# Amiga_Parallel_SD_Rev_3.net
KiCad netlist of a schematic drawn in EAGLE
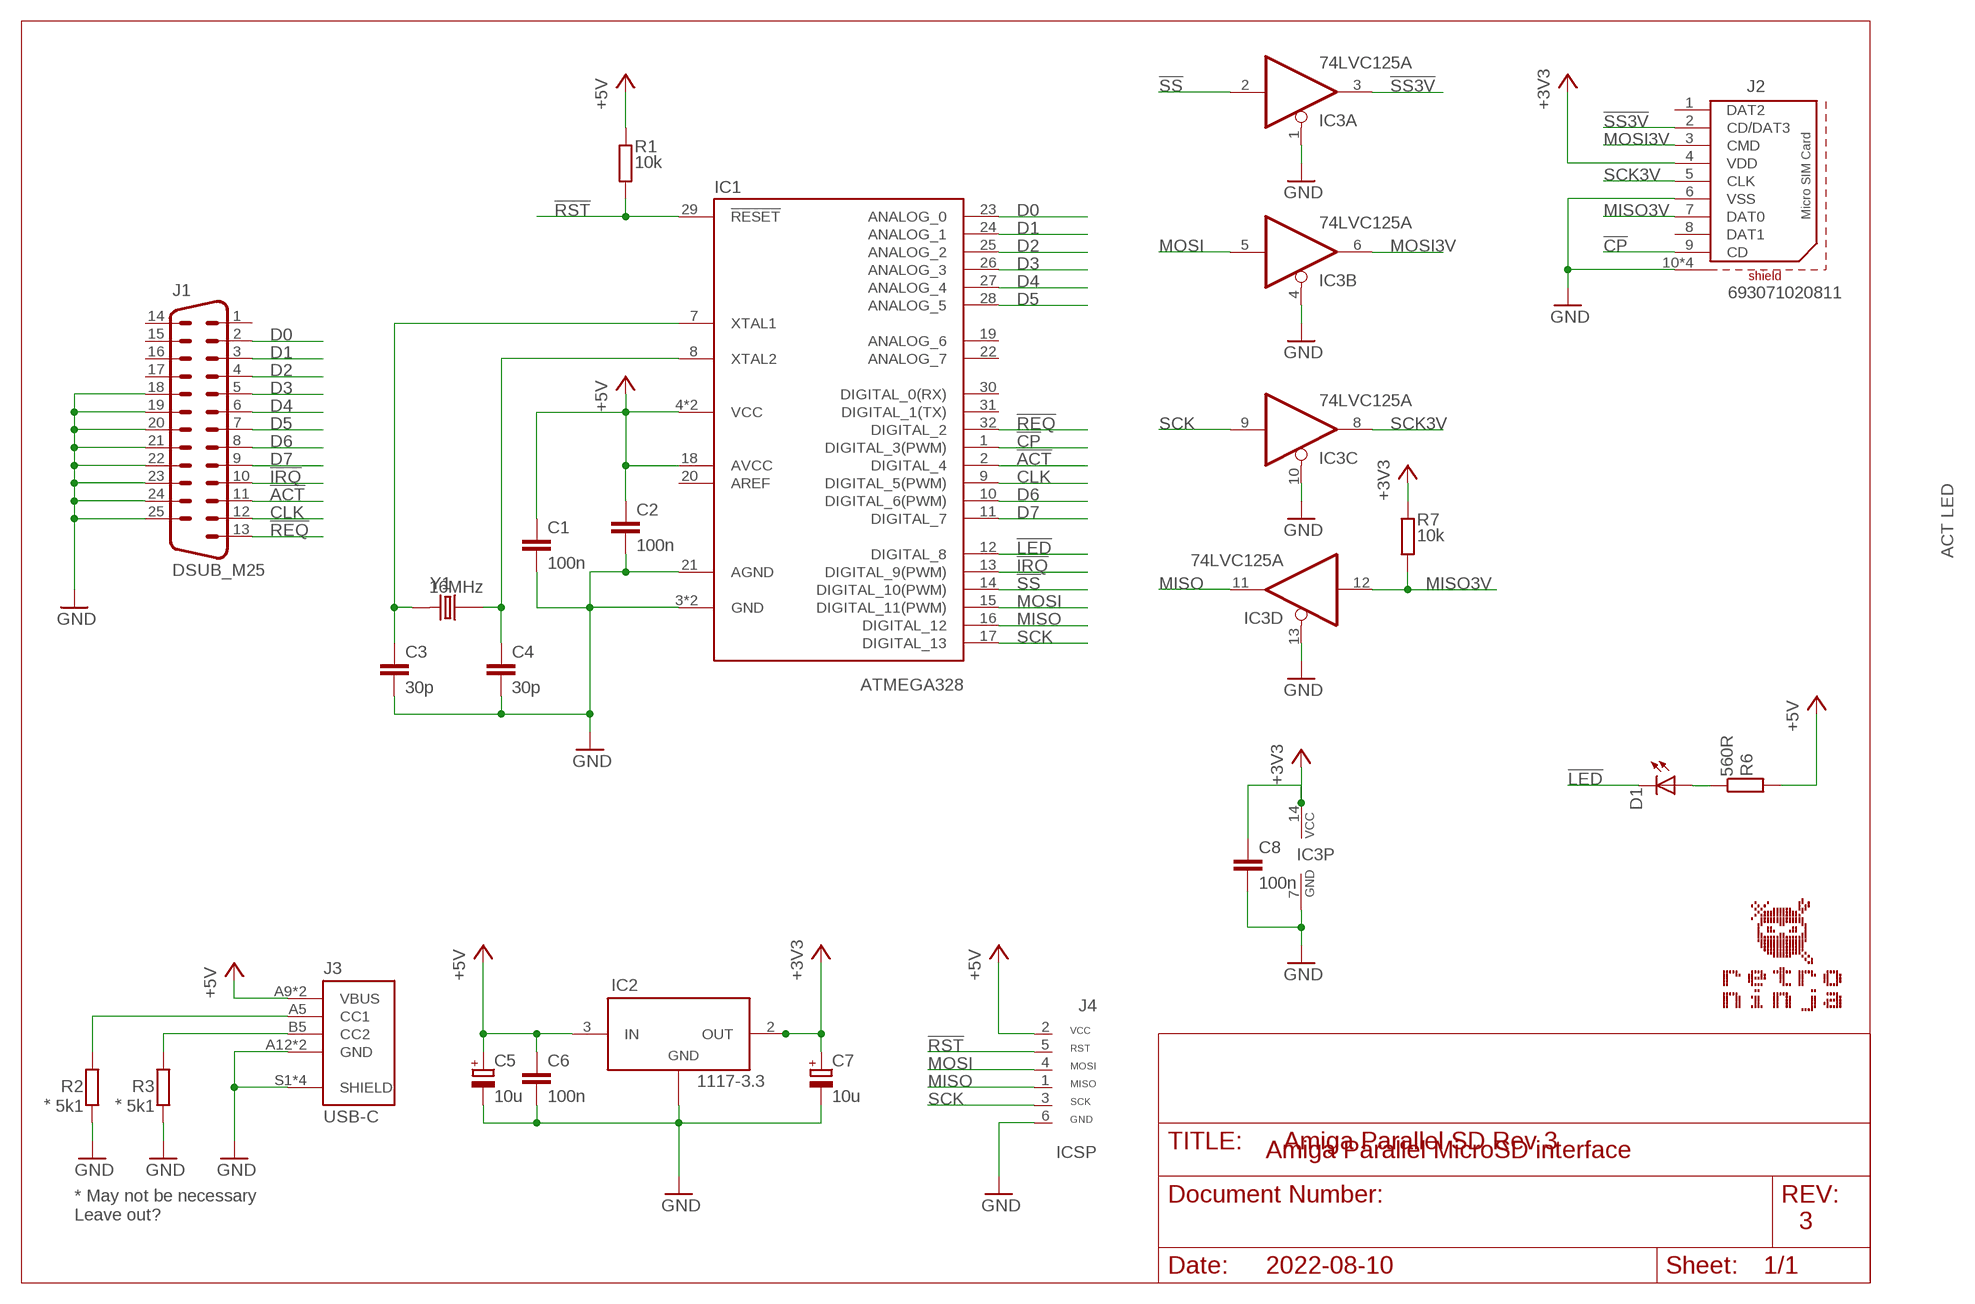
[diagram p0: schematic, sheet 1]

(export (version "E")
  (design (tool "Eeschema 10.0.6"))
  (components
    (comp (ref "C1")
      (value "100n")
      (footprint "eagle-import:C0805")
      (libsource (lib "eagle-import") (part "C-EUC0805"))
    )
    (comp (ref "C2")
      (value "100n")
      (footprint "eagle-import:C0805")
      (libsource (lib "eagle-import") (part "C-EUC0805"))
    )
    (comp (ref "C3")
      (value "30p")
      (footprint "eagle-import:C0805")
      (libsource (lib "eagle-import") (part "C-EUC0805"))
    )
    (comp (ref "C4")
      (value "30p")
      (footprint "eagle-import:C0805")
      (libsource (lib "eagle-import") (part "C-EUC0805"))
    )
    (comp (ref "C5")
      (value "10u")
      (footprint "eagle-import:TANTALUM_0805")
      (libsource (lib "eagle-import") (part "CAPACITOR_POL_TANT_0805"))
    )
    (comp (ref "C6")
      (value "100n")
      (footprint "eagle-import:C0805")
      (libsource (lib "eagle-import") (part "C-EUC0805"))
    )
    (comp (ref "C7")
      (value "10u")
      (footprint "eagle-import:TANTALUM_0805")
      (libsource (lib "eagle-import") (part "CAPACITOR_POL_TANT_0805"))
    )
    (comp (ref "C8")
      (value "100n")
      (footprint "eagle-import:C0805")
      (libsource (lib "eagle-import") (part "C-EUC0805"))
    )
    (comp (ref "D1")
      (value "LED_3MM_GREEN")
      (footprint "eagle-import:LED3MM_GREEN")
      (libsource (lib "eagle-import") (part "LED_3MM_GREEN"))
    )
    (comp (ref "IC1")
      (value "ATMEGA328")
      (footprint "eagle-import:TQFP-32")
      (libsource (lib "eagle-import") (part "ARDUINO_168_328_TQFP"))
    )
    (comp (ref "IC2")
      (value "1117-3.3")
      (footprint "eagle-import:SOT-223")
      (fields
        (field (name "DIGIKEY_PART_NUMBER") "NCP1117ST33T3GOSTR-ND")
        (field (name "MANUFACTURER") "ON Semiconductor")
        (field (name "MPN") "NCP1117ST33T3G")
        (field (name "CREATED_BY") "PCBLayout.com")
      )
      (libsource (lib "eagle-import") (part "NCP1117ST33T3G"))
    )
    (comp (ref "IC3")
      (value "74LVC125A")
      (footprint "eagle-import:SO14")
      (libsource (lib "eagle-import") (part "74125DHC"))
    )
    (comp (ref "J1")
      (value "DSUB_M25")
      (footprint "eagle-import:DSUB_M25D")
      (libsource (lib "eagle-import") (part "DSUB_M25"))
    )
    (comp (ref "J2")
      (value "693071020811")
      (footprint "eagle-import:693071020811")
      (libsource (lib "eagle-import") (part "693071020811"))
    )
    (comp (ref "J3")
      (value "USB-C")
      (footprint "eagle-import:MOLEX_2171750001")
      (fields (field (name "MANUFACTURER") "Molex"))
      (libsource (lib "eagle-import") (part "USB-C"))
    )
    (comp (ref "J4")
      (value "ICSP")
      (footprint "eagle-import:HEADER_2X3_ALT")
      (libsource (lib "eagle-import") (part "ICSP_CONNECTOR_6_ALT"))
    )
    (comp (ref "R1")
      (value "10k")
      (footprint "eagle-import:R0805")
      (libsource (lib "eagle-import") (part "R-EU_R0805"))
    )
    (comp (ref "R2")
      (value "5k1")
      (footprint "eagle-import:R0805")
      (libsource (lib "eagle-import") (part "R-EU_R0805"))
    )
    (comp (ref "R3")
      (value "5k1")
      (footprint "eagle-import:R0805")
      (libsource (lib "eagle-import") (part "R-EU_R0805"))
    )
    (comp (ref "R6")
      (value "560R")
      (footprint "eagle-import:R0805")
      (libsource (lib "eagle-import") (part "R-EU_R0805"))
    )
    (comp (ref "R7")
      (value "10k")
      (footprint "eagle-import:R0805")
      (libsource (lib "eagle-import") (part "R-EU_R0805"))
    )
    (comp (ref "Y1")
      (value "16MHz")
      (footprint "eagle-import:CRYSTAL_SMD-2_7X4X2.3")
      (libsource (lib "eagle-import") (part "CRYSTAL"))
    )
  )
  (nets
    (net (code "1") (name "+3V3") (class "Default")
      (node (ref "C7") (pin "+") (pinfunction "+_+") (pintype "passive"))
      (node (ref "C8") (pin "1") (pinfunction "1_1") (pintype "passive"))
      (node (ref "IC2") (pin "2") (pinfunction "OUT_2") (pintype "output"))
      (node (ref "IC2") (pin "4") (pinfunction "4_4") (pintype "passive"))
      (node (ref "IC3") (pin "14") (pinfunction "VCC_14") (pintype "power_in"))
      (node (ref "J2") (pin "4") (pinfunction "VDD_4") (pintype "bidirectional"))
      (node (ref "R7") (pin "1") (pinfunction "1_1") (pintype "passive"))
    )
    (net (code "2") (name "+5V") (class "Default")
      (node (ref "C1") (pin "1") (pinfunction "1_1") (pintype "passive"))
      (node (ref "C2") (pin "1") (pinfunction "1_1") (pintype "passive"))
      (node (ref "C5") (pin "+") (pinfunction "+_+") (pintype "passive"))
      (node (ref "C6") (pin "1") (pinfunction "1_1") (pintype "passive"))
      (node (ref "IC1") (pin "18") (pinfunction "AVCC_18") (pintype "passive"))
      (node (ref "IC1") (pin "4") (pinfunction "VCC_4") (pintype "passive"))
      (node (ref "IC1") (pin "6") (pinfunction "VCC_6") (pintype "passive"))
      (node (ref "IC2") (pin "3") (pinfunction "IN_3") (pintype "input"))
      (node (ref "J3") (pin "A9") (pinfunction "VBUS_A9") (pintype "power_in"))
      (node (ref "J3") (pin "B9") (pinfunction "VBUS_B9") (pintype "power_in"))
      (node (ref "J4") (pin "2") (pinfunction "VCC_2") (pintype "power_in"))
      (node (ref "R1") (pin "1") (pinfunction "1_1") (pintype "passive"))
      (node (ref "R6") (pin "2") (pinfunction "2_2") (pintype "passive"))
    )
    (net (code "3") (name "/CLK") (class "Default")
      (node (ref "IC1") (pin "9") (pinfunction "DIGITAL_5(PWM)_9") (pintype "bidirectional"))
      (node (ref "J1") (pin "12") (pinfunction "12_12") (pintype "passive"))
    )
    (net (code "4") (name "/D0") (class "Default")
      (node (ref "IC1") (pin "23") (pinfunction "ANALOG_0_23") (pintype "bidirectional"))
      (node (ref "J1") (pin "2") (pinfunction "2_2") (pintype "passive"))
    )
    (net (code "5") (name "/D1") (class "Default")
      (node (ref "IC1") (pin "24") (pinfunction "ANALOG_1_24") (pintype "bidirectional"))
      (node (ref "J1") (pin "3") (pinfunction "3_3") (pintype "passive"))
    )
    (net (code "6") (name "/D2") (class "Default")
      (node (ref "IC1") (pin "25") (pinfunction "ANALOG_2_25") (pintype "bidirectional"))
      (node (ref "J1") (pin "4") (pinfunction "4_4") (pintype "passive"))
    )
    (net (code "7") (name "/D3") (class "Default")
      (node (ref "IC1") (pin "26") (pinfunction "ANALOG_3_26") (pintype "bidirectional"))
      (node (ref "J1") (pin "5") (pinfunction "5_5") (pintype "passive"))
    )
    (net (code "8") (name "/D4") (class "Default")
      (node (ref "IC1") (pin "27") (pinfunction "ANALOG_4_27") (pintype "bidirectional"))
      (node (ref "J1") (pin "6") (pinfunction "6_6") (pintype "passive"))
    )
    (net (code "9") (name "/D5") (class "Default")
      (node (ref "IC1") (pin "28") (pinfunction "ANALOG_5_28") (pintype "bidirectional"))
      (node (ref "J1") (pin "7") (pinfunction "7_7") (pintype "passive"))
    )
    (net (code "10") (name "/D6") (class "Default")
      (node (ref "IC1") (pin "10") (pinfunction "DIGITAL_6(PWM)_10") (pintype "bidirectional"))
      (node (ref "J1") (pin "8") (pinfunction "8_8") (pintype "passive"))
    )
    (net (code "11") (name "/D7") (class "Default")
      (node (ref "IC1") (pin "11") (pinfunction "DIGITAL_7_11") (pintype "bidirectional"))
      (node (ref "J1") (pin "9") (pinfunction "9_9") (pintype "passive"))
    )
    (net (code "12") (name "/MISO") (class "Default")
      (node (ref "IC1") (pin "16") (pinfunction "DIGITAL_12_16") (pintype "bidirectional"))
      (node (ref "IC3") (pin "11") (pinfunction "O_11") (pintype "tri_state"))
      (node (ref "J4") (pin "1") (pinfunction "MISO_1") (pintype "output"))
    )
    (net (code "13") (name "/MISO3V") (class "Default")
      (node (ref "IC3") (pin "12") (pinfunction "I_12") (pintype "input"))
      (node (ref "J2") (pin "7") (pinfunction "DAT0_7") (pintype "bidirectional"))
      (node (ref "R7") (pin "2") (pinfunction "2_2") (pintype "passive"))
    )
    (net (code "14") (name "/MOSI") (class "Default")
      (node (ref "IC1") (pin "15") (pinfunction "DIGITAL_11(PWM)_15") (pintype "bidirectional"))
      (node (ref "IC3") (pin "5") (pinfunction "I_5") (pintype "input"))
      (node (ref "J4") (pin "4") (pinfunction "MOSI_4") (pintype "input"))
    )
    (net (code "15") (name "/MOSI3V") (class "Default")
      (node (ref "IC3") (pin "6") (pinfunction "O_6") (pintype "tri_state"))
      (node (ref "J2") (pin "3") (pinfunction "CMD_3") (pintype "bidirectional"))
    )
    (net (code "16") (name "/SCK") (class "Default")
      (node (ref "IC1") (pin "17") (pinfunction "DIGITAL_13_17") (pintype "bidirectional"))
      (node (ref "IC3") (pin "9") (pinfunction "I_9") (pintype "input"))
      (node (ref "J4") (pin "3") (pinfunction "SCK_3") (pintype "input"))
    )
    (net (code "17") (name "/SCK3V") (class "Default")
      (node (ref "IC3") (pin "8") (pinfunction "O_8") (pintype "tri_state"))
      (node (ref "J2") (pin "5") (pinfunction "CLK_5") (pintype "bidirectional"))
    )
    (net (code "18") (name "/~{ACT}") (class "Default")
      (node (ref "IC1") (pin "2") (pinfunction "DIGITAL_4_2") (pintype "bidirectional"))
      (node (ref "J1") (pin "11") (pinfunction "11_11") (pintype "passive"))
    )
    (net (code "19") (name "/~{CP}") (class "Default")
      (node (ref "IC1") (pin "1") (pinfunction "DIGITAL_3(PWM)_1") (pintype "bidirectional"))
      (node (ref "J2") (pin "9") (pinfunction "CD_9") (pintype "bidirectional"))
    )
    (net (code "20") (name "/~{IRQ}") (class "Default")
      (node (ref "IC1") (pin "13") (pinfunction "DIGITAL_9(PWM)_13") (pintype "bidirectional"))
      (node (ref "J1") (pin "10") (pinfunction "10_10") (pintype "passive"))
    )
    (net (code "21") (name "/~{LED}") (class "Default")
      (node (ref "D1") (pin "K") (pinfunction "C_K") (pintype "passive"))
      (node (ref "IC1") (pin "12") (pinfunction "DIGITAL_8_12") (pintype "bidirectional"))
    )
    (net (code "22") (name "/~{REQ}") (class "Default")
      (node (ref "IC1") (pin "32") (pinfunction "DIGITAL_2_32") (pintype "bidirectional"))
      (node (ref "J1") (pin "13") (pinfunction "13_13") (pintype "passive"))
    )
    (net (code "23") (name "/~{RST}") (class "Default")
      (node (ref "IC1") (pin "29") (pinfunction "~{RESET}_29") (pintype "bidirectional"))
      (node (ref "J4") (pin "5") (pinfunction "RST_5") (pintype "input"))
      (node (ref "R1") (pin "2") (pinfunction "2_2") (pintype "passive"))
    )
    (net (code "24") (name "/~{SS3V}") (class "Default")
      (node (ref "IC3") (pin "3") (pinfunction "O_3") (pintype "tri_state"))
      (node (ref "J2") (pin "2") (pinfunction "CD/DAT3_2") (pintype "bidirectional"))
    )
    (net (code "25") (name "/~{SS}") (class "Default")
      (node (ref "IC1") (pin "14") (pinfunction "DIGITAL_10(PWM)_14") (pintype "bidirectional"))
      (node (ref "IC3") (pin "2") (pinfunction "I_2") (pintype "input"))
    )
    (net (code "26") (name "GND") (class "Default")
      (node (ref "C1") (pin "2") (pinfunction "2_2") (pintype "passive"))
      (node (ref "C2") (pin "2") (pinfunction "2_2") (pintype "passive"))
      (node (ref "C3") (pin "2") (pinfunction "2_2") (pintype "passive"))
      (node (ref "C4") (pin "2") (pinfunction "2_2") (pintype "passive"))
      (node (ref "C5") (pin "-") (pinfunction "-_-") (pintype "passive"))
      (node (ref "C6") (pin "2") (pinfunction "2_2") (pintype "passive"))
      (node (ref "C7") (pin "-") (pinfunction "-_-") (pintype "passive"))
      (node (ref "C8") (pin "2") (pinfunction "2_2") (pintype "passive"))
      (node (ref "IC1") (pin "21") (pinfunction "AGND_21") (pintype "passive"))
      (node (ref "IC1") (pin "3") (pinfunction "GND_3") (pintype "passive"))
      (node (ref "IC1") (pin "5") (pinfunction "GND_5") (pintype "passive"))
      (node (ref "IC2") (pin "1") (pinfunction "ADJ/GND_1") (pintype "power_in"))
      (node (ref "IC3") (pin "1") (pinfunction "OE_1") (pintype "input"))
      (node (ref "IC3") (pin "10") (pinfunction "OE_10") (pintype "input"))
      (node (ref "IC3") (pin "13") (pinfunction "OE_13") (pintype "input"))
      (node (ref "IC3") (pin "4") (pinfunction "OE_4") (pintype "input"))
      (node (ref "IC3") (pin "7") (pinfunction "GND_7") (pintype "power_in"))
      (node (ref "J1") (pin "18") (pinfunction "18_18") (pintype "passive"))
      (node (ref "J1") (pin "19") (pinfunction "19_19") (pintype "passive"))
      (node (ref "J1") (pin "20") (pinfunction "20_20") (pintype "passive"))
      (node (ref "J1") (pin "21") (pinfunction "21_21") (pintype "passive"))
      (node (ref "J1") (pin "22") (pinfunction "22_22") (pintype "passive"))
      (node (ref "J1") (pin "23") (pinfunction "23_23") (pintype "passive"))
      (node (ref "J1") (pin "24") (pinfunction "24_24") (pintype "passive"))
      (node (ref "J1") (pin "25") (pinfunction "25_25") (pintype "passive"))
      (node (ref "J2") (pin "10") (pinfunction "SHIELD_10") (pintype "bidirectional"))
      (node (ref "J2") (pin "11") (pinfunction "SHIELD_11") (pintype "bidirectional"))
      (node (ref "J2") (pin "12") (pinfunction "SHIELD_12") (pintype "bidirectional"))
      (node (ref "J2") (pin "13") (pinfunction "SHIELD_13") (pintype "bidirectional"))
      (node (ref "J2") (pin "6") (pinfunction "VSS_6") (pintype "bidirectional"))
      (node (ref "J3") (pin "A12") (pinfunction "GND_A12") (pintype "power_in"))
      (node (ref "J3") (pin "B12") (pinfunction "GND_B12") (pintype "power_in"))
      (node (ref "J3") (pin "S1") (pinfunction "SHIELD_S1") (pintype "passive"))
      (node (ref "J3") (pin "S2") (pinfunction "SHIELD_S2") (pintype "passive"))
      (node (ref "J3") (pin "S3") (pinfunction "SHIELD_S3") (pintype "passive"))
      (node (ref "J3") (pin "S4") (pinfunction "SHIELD_S4") (pintype "passive"))
      (node (ref "J4") (pin "6") (pinfunction "GND_6") (pintype "power_in"))
      (node (ref "R2") (pin "1") (pinfunction "1_1") (pintype "passive"))
      (node (ref "R3") (pin "1") (pinfunction "1_1") (pintype "passive"))
    )
    (net (code "27") (name "Net-(D1-PadA)") (class "Default")
      (node (ref "D1") (pin "A") (pinfunction "A_A") (pintype "passive"))
      (node (ref "R6") (pin "1") (pinfunction "1_1") (pintype "passive"))
    )
    (net (code "28") (name "Net-(IC1-XTAL1)") (class "Default")
      (node (ref "C3") (pin "1") (pinfunction "1_1") (pintype "passive"))
      (node (ref "IC1") (pin "7") (pinfunction "XTAL1_7") (pintype "bidirectional"))
      (node (ref "Y1") (pin "2") (pinfunction "2_2") (pintype "passive"))
    )
    (net (code "29") (name "Net-(IC1-XTAL2)") (class "Default")
      (node (ref "C4") (pin "1") (pinfunction "1_1") (pintype "passive"))
      (node (ref "IC1") (pin "8") (pinfunction "XTAL2_8") (pintype "bidirectional"))
      (node (ref "Y1") (pin "1") (pinfunction "1_1") (pintype "passive"))
    )
    (net (code "30") (name "Net-(J3-CC1)") (class "Default")
      (node (ref "J3") (pin "A5") (pinfunction "CC1_A5") (pintype "bidirectional"))
      (node (ref "R2") (pin "2") (pinfunction "2_2") (pintype "passive"))
    )
    (net (code "31") (name "Net-(J3-CC2)") (class "Default")
      (node (ref "J3") (pin "B5") (pinfunction "CC2_B5") (pintype "bidirectional"))
      (node (ref "R3") (pin "2") (pinfunction "2_2") (pintype "passive"))
    )
    (net (code "32") (name "unconnected-(IC1-ANALOG_6-Pad19)") (class "Default")
      (node (ref "IC1") (pin "19") (pinfunction "ANALOG_6_19") (pintype "bidirectional"))
    )
    (net (code "33") (name "unconnected-(IC1-ANALOG_7-Pad22)") (class "Default")
      (node (ref "IC1") (pin "22") (pinfunction "ANALOG_7_22") (pintype "bidirectional"))
    )
    (net (code "34") (name "unconnected-(IC1-AREF-Pad20)") (class "Default")
      (node (ref "IC1") (pin "20") (pinfunction "AREF_20") (pintype "passive"))
    )
    (net (code "35") (name "unconnected-(IC1-DIGITAL_0(RX)-Pad30)") (class "Default")
      (node (ref "IC1") (pin "30") (pinfunction "DIGITAL_0(RX)_30") (pintype "bidirectional"))
    )
    (net (code "36") (name "unconnected-(IC1-DIGITAL_1(TX)-Pad31)") (class "Default")
      (node (ref "IC1") (pin "31") (pinfunction "DIGITAL_1(TX)_31") (pintype "bidirectional"))
    )
    (net (code "37") (name "unconnected-(J1-Pad1)") (class "Default")
      (node (ref "J1") (pin "1") (pinfunction "1_1") (pintype "passive"))
    )
    (net (code "38") (name "unconnected-(J1-Pad14)") (class "Default")
      (node (ref "J1") (pin "14") (pinfunction "14_14") (pintype "passive"))
    )
    (net (code "39") (name "unconnected-(J1-Pad15)") (class "Default")
      (node (ref "J1") (pin "15") (pinfunction "15_15") (pintype "passive"))
    )
    (net (code "40") (name "unconnected-(J1-Pad16)") (class "Default")
      (node (ref "J1") (pin "16") (pinfunction "16_16") (pintype "passive"))
    )
    (net (code "41") (name "unconnected-(J1-Pad17)") (class "Default")
      (node (ref "J1") (pin "17") (pinfunction "17_17") (pintype "passive"))
    )
    (net (code "42") (name "unconnected-(J2-DAT1-Pad8)") (class "Default")
      (node (ref "J2") (pin "8") (pinfunction "DAT1_8") (pintype "bidirectional"))
    )
    (net (code "43") (name "unconnected-(J2-DAT2-Pad1)") (class "Default")
      (node (ref "J2") (pin "1") (pinfunction "DAT2_1") (pintype "bidirectional"))
    )
  )
)
